# SimpleMonitorUSBAER.net
KiCad netlist of a schematic drawn in Altium Designer
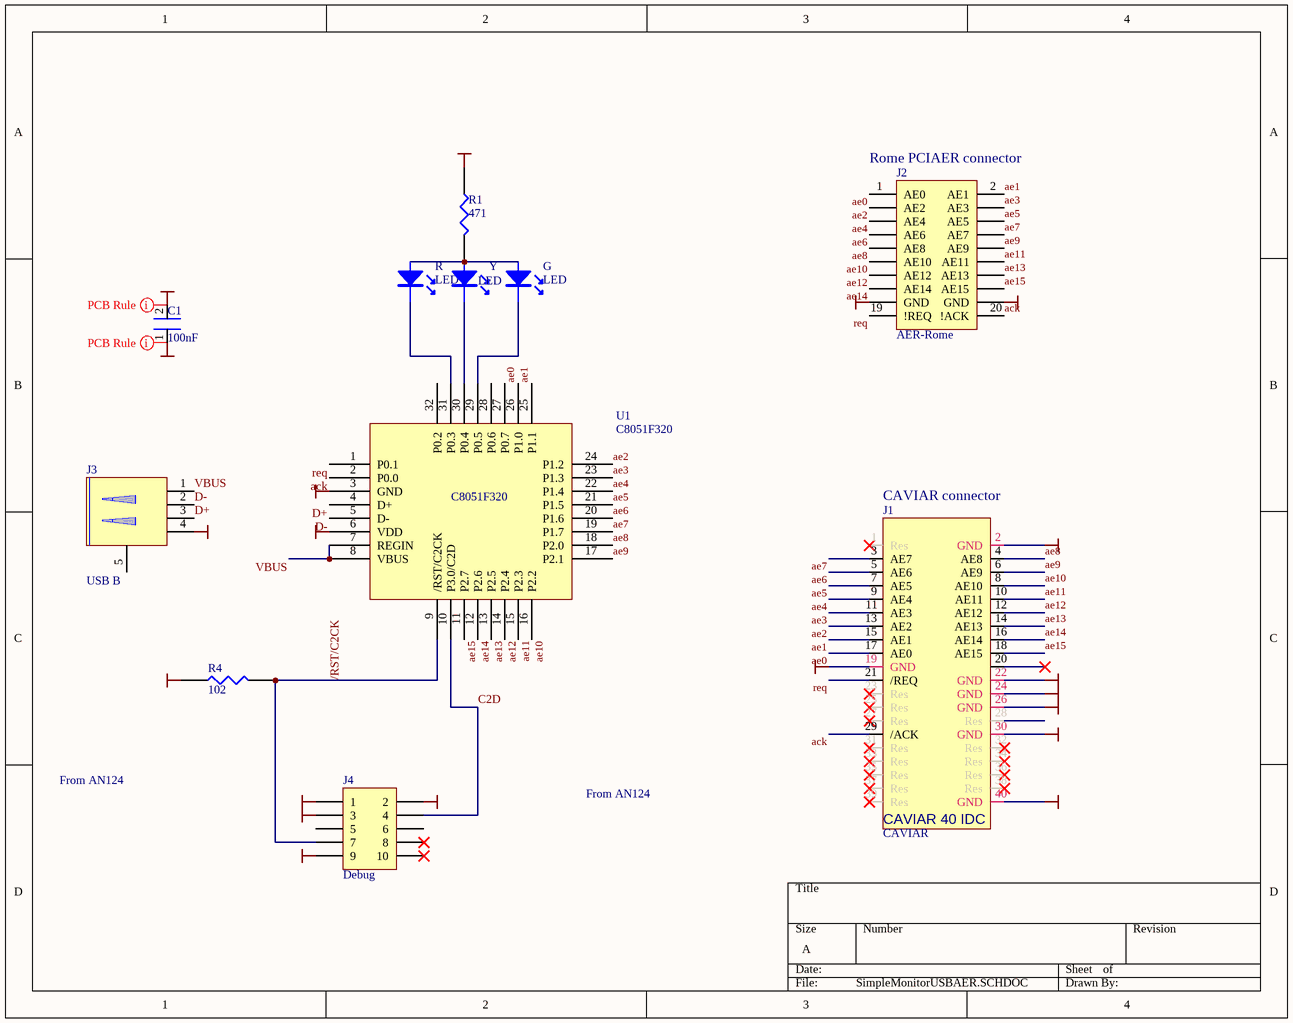
[diagram p0: SimpleMonitorUSBAER.SCHDOC]

(export (version "E")
  (design (tool "Eeschema 10.0.6"))
  (components
    (comp (ref "C1")
      (value "100nF")
      (footprint "CC3216-1206")
      (libsource (lib "tobi SCHEMATIC") (part "CAPCHIP"))
    )
    (comp (ref "G")
      (value "LED")
      (footprint "0805LED")
      (description "LED, SMT 3mm by 1.5mm")
      (libsource (lib "*") (part "LED"))
    )
    (comp (ref "J1")
      (value "CAVIAR")
      (footprint "HDR2X20 with shell")
      (description "CAVIAR 40 pin IDC header")
      (libsource (lib "tobi SCHEMATIC") (part "CAVIAR 40 IDC"))
    )
    (comp (ref "J2")
      (value "AER-Rome")
      (footprint "HDR10x2 w/clips")
      (description "AER-Rome 20-Pin, Dual row, with IDC mounting clips")
      (fields (field (name "MANUFACTURER") "Generic Components"))
      (libsource (lib "tobi SCHEMATIC") (part "Header AER-ROME"))
    )
    (comp (ref "J3")
      (value "USB B")
      (footprint "usb")
      (description "USB TypB")
      (libsource (lib "DAC") (part "USB"))
    )
    (comp (ref "J4")
      (value "Debug")
      (footprint "HDR2X5")
      (description "Header, 5-Pin, Dual row")
      (fields (field (name "PUBLISHER") "Altium Limited"))
      (libsource (lib "Miscellaneous Connectors") (part "Header 5X2"))
    )
    (comp (ref "R")
      (value "LED")
      (footprint "0805LED")
      (description "LED, SMT 3mm by 1.5mm")
      (libsource (lib "*") (part "LED"))
    )
    (comp (ref "R1") (value "471") (footprint "CR2012-0805") (libsource (lib "*") (part "RES1")))
    (comp (ref "R4") (value "102") (footprint "CR2012-0805") (libsource (lib "*") (part "RES1")))
    (comp (ref "U1")
      (value "C8051F320")
      (footprint "TQFP32")
      (description "Silicon Labs USB Microcontroller")
      (libsource (lib "tobi SCHEMATIC") (part "C8051F320"))
    )
    (comp (ref "Y")
      (value "LED")
      (footprint "0805LED")
      (description "LED, SMT 3mm by 1.5mm")
      (libsource (lib "*") (part "LED"))
    )
  )
  (nets
    (net (code "1") (name "/C2D") (class "Default")
      (node (ref "J4") (pin "4") (pinfunction "4_4") (pintype "passive"))
      (node (ref "U1") (pin "10") (pinfunction "P3.0/C2D_10") (pintype "passive"))
    )
    (net (code "2") (name "/D+") (class "Default")
      (node (ref "J3") (pin "3") (pintype "passive"))
      (node (ref "U1") (pin "4") (pinfunction "D+_4") (pintype "passive"))
    )
    (net (code "3") (name "/D-") (class "Default")
      (node (ref "J3") (pin "2") (pintype "passive"))
      (node (ref "U1") (pin "5") (pinfunction "D-_5") (pintype "passive"))
    )
    (net (code "4") (name "/VBUS") (class "Default")
      (node (ref "J3") (pin "1") (pintype "passive"))
      (node (ref "U1") (pin "7") (pinfunction "REGIN_7") (pintype "passive"))
      (node (ref "U1") (pin "8") (pinfunction "VBUS_8") (pintype "passive"))
    )
    (net (code "5") (name "/ack") (class "Default")
      (node (ref "J1") (pin "29") (pinfunction "/ACK_29") (pintype "tri_state"))
      (node (ref "J2") (pin "20") (pinfunction "!ACK_20") (pintype "passive"))
      (node (ref "U1") (pin "2") (pinfunction "P0.0_2") (pintype "passive"))
    )
    (net (code "6") (name "/ae0") (class "Default")
      (node (ref "J1") (pin "17") (pinfunction "AE0_17") (pintype "tri_state"))
      (node (ref "J2") (pin "1") (pinfunction "AE0_1") (pintype "passive"))
      (node (ref "U1") (pin "26") (pinfunction "P1.0_26") (pintype "passive"))
    )
    (net (code "7") (name "/ae1") (class "Default")
      (node (ref "J1") (pin "15") (pinfunction "AE1_15") (pintype "tri_state"))
      (node (ref "J2") (pin "2") (pinfunction "AE1_2") (pintype "passive"))
      (node (ref "U1") (pin "25") (pinfunction "P1.1_25") (pintype "passive"))
    )
    (net (code "8") (name "/ae2") (class "Default")
      (node (ref "J1") (pin "13") (pinfunction "AE2_13") (pintype "tri_state"))
      (node (ref "J2") (pin "3") (pinfunction "AE2_3") (pintype "passive"))
      (node (ref "U1") (pin "24") (pinfunction "P1.2_24") (pintype "passive"))
    )
    (net (code "9") (name "/ae3") (class "Default")
      (node (ref "J1") (pin "11") (pinfunction "AE3_11") (pintype "tri_state"))
      (node (ref "J2") (pin "4") (pinfunction "AE3_4") (pintype "passive"))
      (node (ref "U1") (pin "23") (pinfunction "P1.3_23") (pintype "passive"))
    )
    (net (code "10") (name "/ae4") (class "Default")
      (node (ref "J1") (pin "9") (pinfunction "AE4_9") (pintype "tri_state"))
      (node (ref "J2") (pin "5") (pinfunction "AE4_5") (pintype "passive"))
      (node (ref "U1") (pin "22") (pinfunction "P1.4_22") (pintype "passive"))
    )
    (net (code "11") (name "/ae5") (class "Default")
      (node (ref "J1") (pin "7") (pinfunction "AE5_7") (pintype "tri_state"))
      (node (ref "J2") (pin "6") (pinfunction "AE5_6") (pintype "passive"))
      (node (ref "U1") (pin "21") (pinfunction "P1.5_21") (pintype "passive"))
    )
    (net (code "12") (name "/ae6") (class "Default")
      (node (ref "J1") (pin "5") (pinfunction "AE6_5") (pintype "tri_state"))
      (node (ref "J2") (pin "7") (pinfunction "AE6_7") (pintype "passive"))
      (node (ref "U1") (pin "20") (pinfunction "P1.6_20") (pintype "passive"))
    )
    (net (code "13") (name "/ae7") (class "Default")
      (node (ref "J1") (pin "3") (pinfunction "AE7_3") (pintype "passive"))
      (node (ref "J2") (pin "8") (pinfunction "AE7_8") (pintype "passive"))
      (node (ref "U1") (pin "19") (pinfunction "P1.7_19") (pintype "passive"))
    )
    (net (code "14") (name "/ae8") (class "Default")
      (node (ref "J1") (pin "4") (pinfunction "AE8_4") (pintype "tri_state"))
      (node (ref "J2") (pin "9") (pinfunction "AE8_9") (pintype "passive"))
      (node (ref "U1") (pin "18") (pinfunction "P2.0_18") (pintype "passive"))
    )
    (net (code "15") (name "/ae9") (class "Default")
      (node (ref "J1") (pin "6") (pinfunction "AE9_6") (pintype "tri_state"))
      (node (ref "J2") (pin "10") (pinfunction "AE9_10") (pintype "passive"))
      (node (ref "U1") (pin "17") (pinfunction "P2.1_17") (pintype "passive"))
    )
    (net (code "16") (name "/ae10") (class "Default")
      (node (ref "J1") (pin "8") (pinfunction "AE10_8") (pintype "tri_state"))
      (node (ref "J2") (pin "11") (pinfunction "AE10_11") (pintype "passive"))
      (node (ref "U1") (pin "16") (pinfunction "P2.2_16") (pintype "passive"))
    )
    (net (code "17") (name "/ae11") (class "Default")
      (node (ref "J1") (pin "10") (pinfunction "AE11_10") (pintype "tri_state"))
      (node (ref "J2") (pin "12") (pinfunction "AE11_12") (pintype "passive"))
      (node (ref "U1") (pin "15") (pinfunction "P2.3_15") (pintype "passive"))
    )
    (net (code "18") (name "/ae12") (class "Default")
      (node (ref "J1") (pin "12") (pinfunction "AE12_12") (pintype "tri_state"))
      (node (ref "J2") (pin "13") (pinfunction "AE12_13") (pintype "passive"))
      (node (ref "U1") (pin "14") (pinfunction "P2.4_14") (pintype "passive"))
    )
    (net (code "19") (name "/ae13") (class "Default")
      (node (ref "J1") (pin "14") (pinfunction "AE13_14") (pintype "tri_state"))
      (node (ref "J2") (pin "14") (pinfunction "AE13_14") (pintype "passive"))
      (node (ref "U1") (pin "13") (pinfunction "P2.5_13") (pintype "passive"))
    )
    (net (code "20") (name "/ae14") (class "Default")
      (node (ref "J1") (pin "16") (pinfunction "AE14_16") (pintype "tri_state"))
      (node (ref "J2") (pin "15") (pinfunction "AE14_15") (pintype "passive"))
      (node (ref "U1") (pin "12") (pinfunction "P2.6_12") (pintype "passive"))
    )
    (net (code "21") (name "/ae15") (class "Default")
      (node (ref "J1") (pin "18") (pinfunction "AE15_18") (pintype "tri_state"))
      (node (ref "J2") (pin "16") (pinfunction "AE15_16") (pintype "passive"))
      (node (ref "U1") (pin "11") (pinfunction "P2.7_11") (pintype "passive"))
    )
    (net (code "22") (name "/req") (class "Default")
      (node (ref "J1") (pin "21") (pinfunction "/REQ_21") (pintype "tri_state"))
      (node (ref "J2") (pin "19") (pinfunction "!REQ_19") (pintype "passive"))
      (node (ref "U1") (pin "1") (pinfunction "P0.1_1") (pintype "passive"))
    )
    (net (code "23") (name "/{slash}RST{slash}C2CK") (class "Default")
      (node (ref "J4") (pin "7") (pinfunction "7_7") (pintype "passive"))
      (node (ref "R4") (pin "2") (pinfunction "2_2") (pintype "passive"))
      (node (ref "U1") (pin "9") (pinfunction "/RST/C2CK_9") (pintype "passive"))
    )
    (net (code "24") (name "GND") (class "Default")
      (node (ref "C1") (pin "1") (pintype "passive"))
      (node (ref "J1") (pin "19") (pinfunction "GND_19") (pintype "power_in"))
      (node (ref "J1") (pin "2") (pinfunction "GND_2") (pintype "power_in"))
      (node (ref "J1") (pin "22") (pinfunction "GND_22") (pintype "power_in"))
      (node (ref "J1") (pin "24") (pinfunction "GND_24") (pintype "power_in"))
      (node (ref "J1") (pin "26") (pinfunction "GND_26") (pintype "power_in"))
      (node (ref "J1") (pin "30") (pinfunction "GND_30") (pintype "power_in"))
      (node (ref "J1") (pin "40") (pinfunction "GND_40") (pintype "power_in"))
      (node (ref "J2") (pin "17") (pinfunction "GND_17") (pintype "passive"))
      (node (ref "J2") (pin "18") (pinfunction "GND_18") (pintype "passive"))
      (node (ref "J3") (pin "4") (pintype "passive"))
      (node (ref "J4") (pin "2") (pinfunction "2_2") (pintype "passive"))
      (node (ref "J4") (pin "3") (pinfunction "3_3") (pintype "passive"))
      (node (ref "J4") (pin "9") (pinfunction "9_9") (pintype "passive"))
      (node (ref "U1") (pin "3") (pinfunction "GND_3") (pintype "passive"))
    )
    (net (code "25") (name "Net-(G-1)") (class "Default")
      (node (ref "G") (pin "+") (pinfunction "1_+") (pintype "passive"))
      (node (ref "R") (pin "+") (pinfunction "1_+") (pintype "passive"))
      (node (ref "R1") (pin "2") (pinfunction "2_2") (pintype "passive"))
      (node (ref "Y") (pin "+") (pinfunction "1_+") (pintype "passive"))
    )
    (net (code "26") (name "Net-(G-2)") (class "Default")
      (node (ref "G") (pin "-") (pinfunction "2_-") (pintype "passive"))
      (node (ref "U1") (pin "29") (pinfunction "P0.5_29") (pintype "passive"))
    )
    (net (code "27") (name "Net-(R-2)") (class "Default")
      (node (ref "R") (pin "-") (pinfunction "2_-") (pintype "passive"))
      (node (ref "U1") (pin "31") (pinfunction "P0.3_31") (pintype "passive"))
    )
    (net (code "28") (name "Net-(U1-P0.4)") (class "Default")
      (node (ref "U1") (pin "30") (pinfunction "P0.4_30") (pintype "passive"))
      (node (ref "Y") (pin "-") (pinfunction "2_-") (pintype "passive"))
    )
    (net (code "29") (name "VDD") (class "Default")
      (node (ref "C1") (pin "2") (pintype "passive"))
      (node (ref "J4") (pin "1") (pinfunction "1_1") (pintype "passive"))
      (node (ref "R1") (pin "1") (pinfunction "1_1") (pintype "passive"))
      (node (ref "R4") (pin "1") (pinfunction "1_1") (pintype "passive"))
      (node (ref "U1") (pin "6") (pinfunction "VDD_6") (pintype "passive"))
    )
    (net (code "30") (name "unconnected-(J1-Pad20)") (class "Default")
      (node (ref "J1") (pin "20") (pintype "tri_state+no_connect"))
    )
    (net (code "31") (name "unconnected-(J1-Res-Pad1)") (class "Default")
      (node (ref "J1") (pin "1") (pinfunction "Res_1") (pintype "passive+no_connect"))
    )
    (net (code "32") (name "unconnected-(J1-Res-Pad23)") (class "Default")
      (node (ref "J1") (pin "23") (pinfunction "Res_23") (pintype "passive+no_connect"))
    )
    (net (code "33") (name "unconnected-(J1-Res-Pad25)") (class "Default")
      (node (ref "J1") (pin "25") (pinfunction "Res_25") (pintype "passive+no_connect"))
    )
    (net (code "34") (name "unconnected-(J1-Res-Pad27)") (class "Default")
      (node (ref "J1") (pin "27") (pinfunction "Res_27") (pintype "passive+no_connect"))
    )
    (net (code "35") (name "unconnected-(J1-Res-Pad28)") (class "Default")
      (node (ref "J1") (pin "28") (pinfunction "Res_28") (pintype "passive"))
    )
    (net (code "36") (name "unconnected-(J1-Res-Pad31)") (class "Default")
      (node (ref "J1") (pin "31") (pinfunction "Res_31") (pintype "passive+no_connect"))
    )
    (net (code "37") (name "unconnected-(J1-Res-Pad32)") (class "Default")
      (node (ref "J1") (pin "32") (pinfunction "Res_32") (pintype "passive+no_connect"))
    )
    (net (code "38") (name "unconnected-(J1-Res-Pad33)") (class "Default")
      (node (ref "J1") (pin "33") (pinfunction "Res_33") (pintype "passive+no_connect"))
    )
    (net (code "39") (name "unconnected-(J1-Res-Pad34)") (class "Default")
      (node (ref "J1") (pin "34") (pinfunction "Res_34") (pintype "passive+no_connect"))
    )
    (net (code "40") (name "unconnected-(J1-Res-Pad35)") (class "Default")
      (node (ref "J1") (pin "35") (pinfunction "Res_35") (pintype "passive+no_connect"))
    )
    (net (code "41") (name "unconnected-(J1-Res-Pad36)") (class "Default")
      (node (ref "J1") (pin "36") (pinfunction "Res_36") (pintype "passive+no_connect"))
    )
    (net (code "42") (name "unconnected-(J1-Res-Pad37)") (class "Default")
      (node (ref "J1") (pin "37") (pinfunction "Res_37") (pintype "passive+no_connect"))
    )
    (net (code "43") (name "unconnected-(J1-Res-Pad38)") (class "Default")
      (node (ref "J1") (pin "38") (pinfunction "Res_38") (pintype "passive+no_connect"))
    )
    (net (code "44") (name "unconnected-(J1-Res-Pad39)") (class "Default")
      (node (ref "J1") (pin "39") (pinfunction "Res_39") (pintype "passive+no_connect"))
    )
    (net (code "45") (name "unconnected-(J3-Pad5)") (class "Default")
      (node (ref "J3") (pin "5") (pintype "passive"))
    )
    (net (code "46") (name "unconnected-(J4-Pad5)") (class "Default")
      (node (ref "J4") (pin "5") (pinfunction "5_5") (pintype "passive"))
    )
    (net (code "47") (name "unconnected-(J4-Pad6)") (class "Default")
      (node (ref "J4") (pin "6") (pinfunction "6_6") (pintype "passive"))
    )
    (net (code "48") (name "unconnected-(J4-Pad8)") (class "Default")
      (node (ref "J4") (pin "8") (pinfunction "8_8") (pintype "passive+no_connect"))
    )
    (net (code "49") (name "unconnected-(J4-Pad10)") (class "Default")
      (node (ref "J4") (pin "10") (pinfunction "10_10") (pintype "passive+no_connect"))
    )
    (net (code "50") (name "unconnected-(U1-P0.2-Pad32)") (class "Default")
      (node (ref "U1") (pin "32") (pinfunction "P0.2_32") (pintype "passive"))
    )
    (net (code "51") (name "unconnected-(U1-P0.6-Pad28)") (class "Default")
      (node (ref "U1") (pin "28") (pinfunction "P0.6_28") (pintype "passive"))
    )
    (net (code "52") (name "unconnected-(U1-P0.7-Pad27)") (class "Default")
      (node (ref "U1") (pin "27") (pinfunction "P0.7_27") (pintype "passive"))
    )
  )
)
